# ledbord.net
KiCad netlist of a schematic drawn in EAGLE
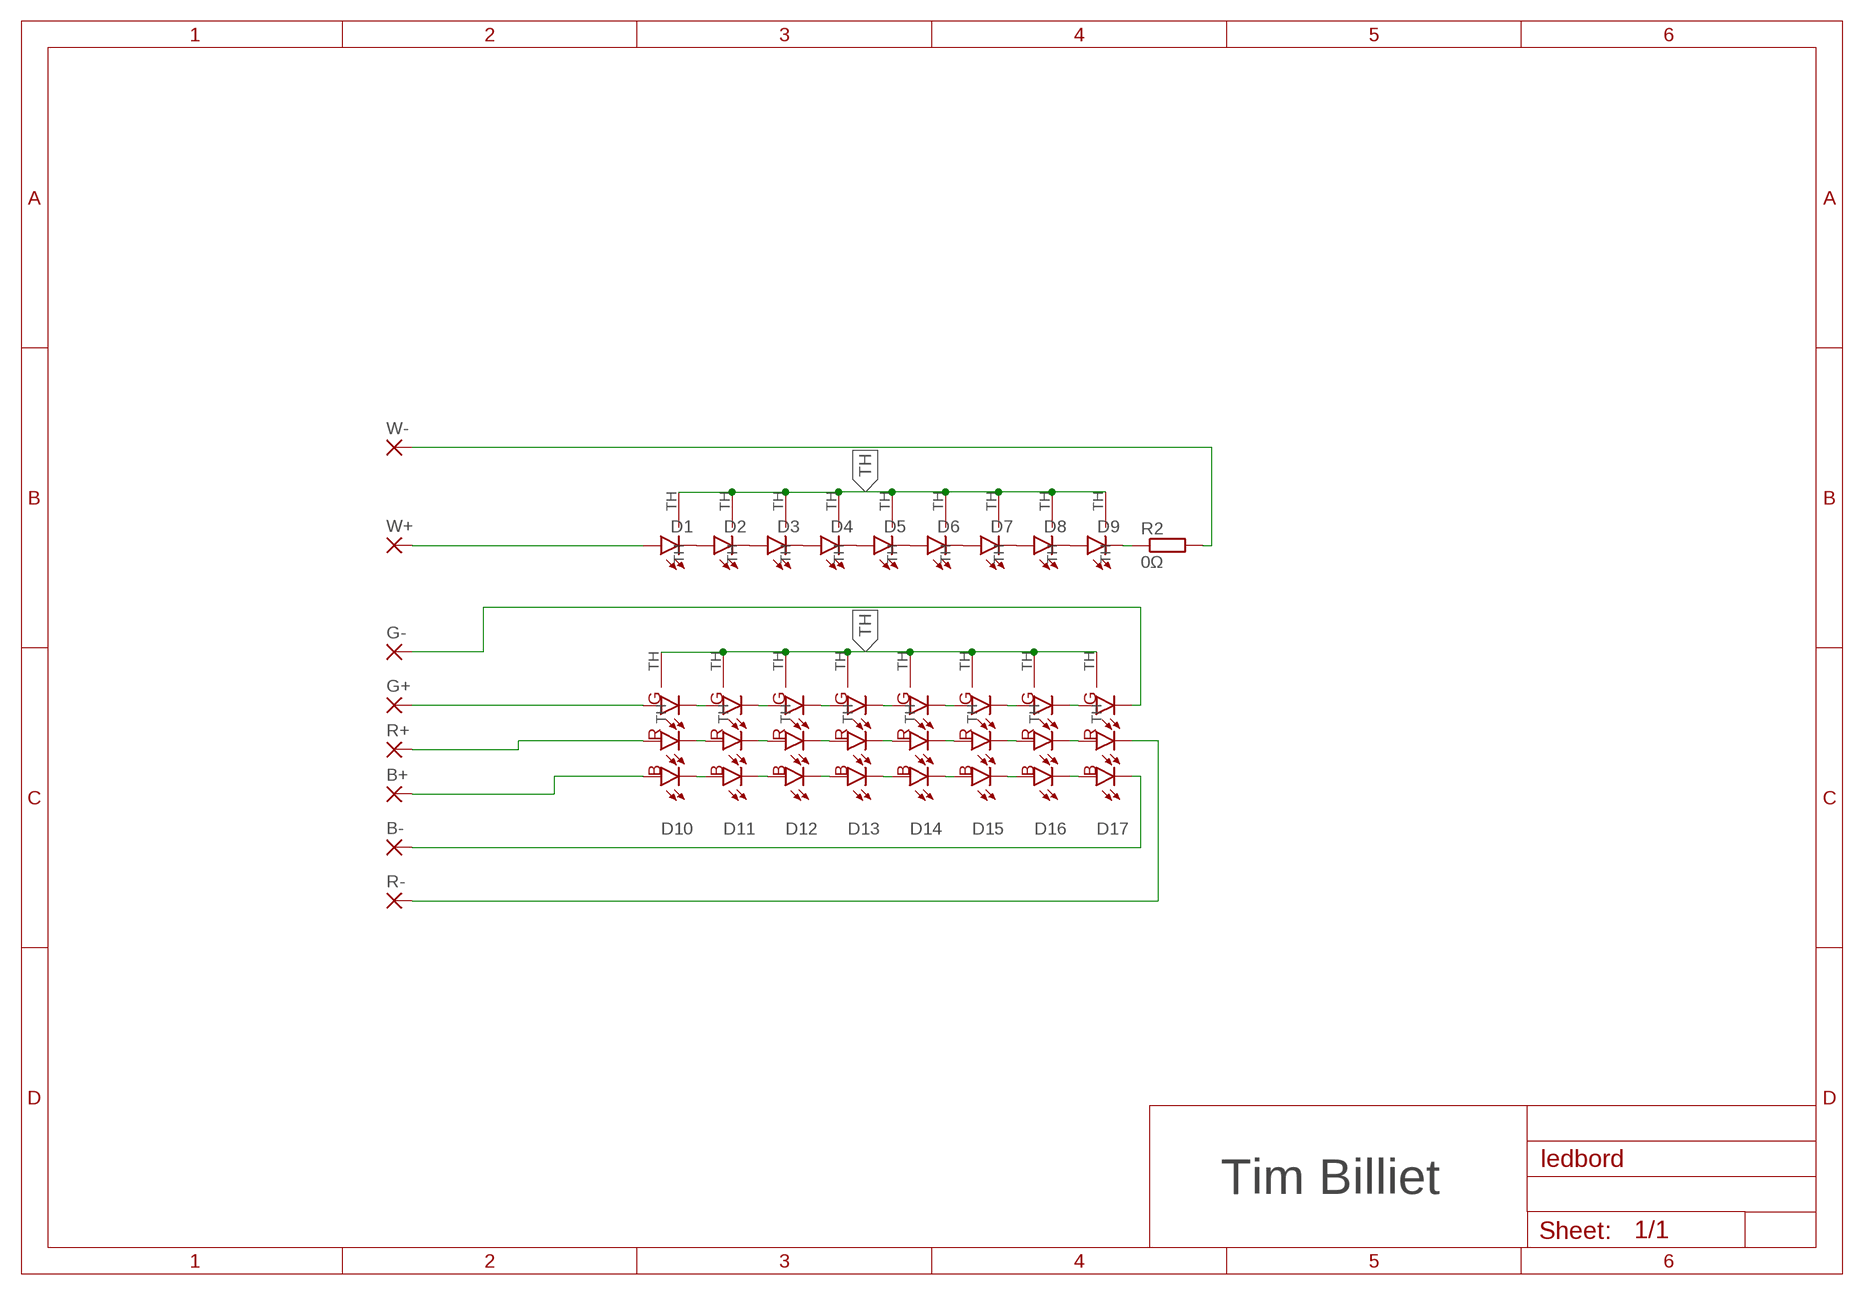
[diagram p0: schematic, sheet 1]

(export (version "E")
  (design (tool "Eeschema 10.0.6"))
  (components
    (comp (ref "B+")
      (value "SMD5")
      (footprint "eagle-import:SMD2,54-5,08")
      (libsource (lib "eagle-import") (part "SMD5"))
    )
    (comp (ref "B-")
      (value "SMD5")
      (footprint "eagle-import:SMD2,54-5,08")
      (libsource (lib "eagle-import") (part "SMD5"))
    )
    (comp (ref "D1")
      (value "HL-C3535F77W1GA-LED")
      (footprint "eagle-import:HL-C3535F77W1GA-LED")
      (libsource (lib "eagle-import") (part "HL-C3535F77W1GA-LED"))
    )
    (comp (ref "D2")
      (value "HL-C3535F77W1GA-LED")
      (footprint "eagle-import:HL-C3535F77W1GA-LED")
      (libsource (lib "eagle-import") (part "HL-C3535F77W1GA-LED"))
    )
    (comp (ref "D3")
      (value "HL-C3535F77W1GA-LED")
      (footprint "eagle-import:HL-C3535F77W1GA-LED")
      (libsource (lib "eagle-import") (part "HL-C3535F77W1GA-LED"))
    )
    (comp (ref "D4")
      (value "HL-C3535F77W1GA-LED")
      (footprint "eagle-import:HL-C3535F77W1GA-LED")
      (libsource (lib "eagle-import") (part "HL-C3535F77W1GA-LED"))
    )
    (comp (ref "D5")
      (value "HL-C3535F77W1GA-LED")
      (footprint "eagle-import:HL-C3535F77W1GA-LED")
      (libsource (lib "eagle-import") (part "HL-C3535F77W1GA-LED"))
    )
    (comp (ref "D6")
      (value "HL-C3535F77W1GA-LED")
      (footprint "eagle-import:HL-C3535F77W1GA-LED")
      (libsource (lib "eagle-import") (part "HL-C3535F77W1GA-LED"))
    )
    (comp (ref "D7")
      (value "HL-C3535F77W1GA-LED")
      (footprint "eagle-import:HL-C3535F77W1GA-LED")
      (libsource (lib "eagle-import") (part "HL-C3535F77W1GA-LED"))
    )
    (comp (ref "D8")
      (value "HL-C3535F77W1GA-LED")
      (footprint "eagle-import:HL-C3535F77W1GA-LED")
      (libsource (lib "eagle-import") (part "HL-C3535F77W1GA-LED"))
    )
    (comp (ref "D9")
      (value "HL-C3535F77W1GA-LED")
      (footprint "eagle-import:HL-C3535F77W1GA-LED")
      (libsource (lib "eagle-import") (part "HL-C3535F77W1GA-LED"))
    )
    (comp (ref "D10")
      (value "TJ-S5050UGEW5TLCBRG-A5")
      (footprint "eagle-import:TJ-S5050UGEW5TLCBRG-A5")
      (libsource (lib "eagle-import") (part "TJ-S5050UGEW5TLCBRG-A5"))
    )
    (comp (ref "D11")
      (value "TJ-S5050UGEW5TLCBRG-A5")
      (footprint "eagle-import:TJ-S5050UGEW5TLCBRG-A5")
      (libsource (lib "eagle-import") (part "TJ-S5050UGEW5TLCBRG-A5"))
    )
    (comp (ref "D12")
      (value "TJ-S5050UGEW5TLCBRG-A5")
      (footprint "eagle-import:TJ-S5050UGEW5TLCBRG-A5")
      (libsource (lib "eagle-import") (part "TJ-S5050UGEW5TLCBRG-A5"))
    )
    (comp (ref "D13")
      (value "TJ-S5050UGEW5TLCBRG-A5")
      (footprint "eagle-import:TJ-S5050UGEW5TLCBRG-A5")
      (libsource (lib "eagle-import") (part "TJ-S5050UGEW5TLCBRG-A5"))
    )
    (comp (ref "D14")
      (value "TJ-S5050UGEW5TLCBRG-A5")
      (footprint "eagle-import:TJ-S5050UGEW5TLCBRG-A5")
      (libsource (lib "eagle-import") (part "TJ-S5050UGEW5TLCBRG-A5"))
    )
    (comp (ref "D15")
      (value "TJ-S5050UGEW5TLCBRG-A5")
      (footprint "eagle-import:TJ-S5050UGEW5TLCBRG-A5")
      (libsource (lib "eagle-import") (part "TJ-S5050UGEW5TLCBRG-A5"))
    )
    (comp (ref "D16")
      (value "TJ-S5050UGEW5TLCBRG-A5")
      (footprint "eagle-import:TJ-S5050UGEW5TLCBRG-A5")
      (libsource (lib "eagle-import") (part "TJ-S5050UGEW5TLCBRG-A5"))
    )
    (comp (ref "D17")
      (value "TJ-S5050UGEW5TLCBRG-A5")
      (footprint "eagle-import:TJ-S5050UGEW5TLCBRG-A5")
      (libsource (lib "eagle-import") (part "TJ-S5050UGEW5TLCBRG-A5"))
    )
    (comp (ref "G+")
      (value "SMD5")
      (footprint "eagle-import:SMD2,54-5,08")
      (libsource (lib "eagle-import") (part "SMD5"))
    )
    (comp (ref "G-")
      (value "SMD5")
      (footprint "eagle-import:SMD2,54-5,08")
      (libsource (lib "eagle-import") (part "SMD5"))
    )
    (comp (ref "R+")
      (value "SMD5")
      (footprint "eagle-import:SMD2,54-5,08")
      (libsource (lib "eagle-import") (part "SMD5"))
    )
    (comp (ref "R-")
      (value "SMD5")
      (footprint "eagle-import:SMD2,54-5,08")
      (libsource (lib "eagle-import") (part "SMD5"))
    )
    (comp (ref "R2")
      (value "0Ω")
      (footprint "eagle-import:R2512")
      (libsource (lib "eagle-import") (part "R-EU_R2512"))
    )
    (comp (ref "W+")
      (value "SMD5")
      (footprint "eagle-import:SMD2,54-5,08")
      (libsource (lib "eagle-import") (part "SMD5"))
    )
    (comp (ref "W-")
      (value "SMD5")
      (footprint "eagle-import:SMD2,54-5,08")
      (libsource (lib "eagle-import") (part "SMD5"))
    )
  )
  (nets
    (net (code "1") (name "Net-(B+-P)") (class "Default")
      (node (ref "B+") (pin "1") (pinfunction "P_1") (pintype "passive"))
      (node (ref "D10") (pin "P6") (pinfunction "6B+_P6") (pintype "passive"))
    )
    (net (code "2") (name "Net-(B--P)") (class "Default")
      (node (ref "B-") (pin "1") (pinfunction "P_1") (pintype "passive"))
      (node (ref "D17") (pin "P1") (pinfunction "1B-_P1") (pintype "passive"))
    )
    (net (code "3") (name "Net-(D1-A)") (class "Default")
      (node (ref "D1") (pin "P$1") (pinfunction "A_P$1") (pintype "passive"))
      (node (ref "W+") (pin "1") (pinfunction "P_1") (pintype "passive"))
    )
    (net (code "4") (name "Net-(D1-C)") (class "Default")
      (node (ref "D1") (pin "P$2") (pinfunction "C_P$2") (pintype "passive"))
      (node (ref "D2") (pin "P$1") (pinfunction "A_P$1") (pintype "passive"))
    )
    (net (code "5") (name "Net-(D2-C)") (class "Default")
      (node (ref "D2") (pin "P$2") (pinfunction "C_P$2") (pintype "passive"))
      (node (ref "D3") (pin "P$1") (pinfunction "A_P$1") (pintype "passive"))
    )
    (net (code "6") (name "Net-(D3-C)") (class "Default")
      (node (ref "D3") (pin "P$2") (pinfunction "C_P$2") (pintype "passive"))
      (node (ref "D4") (pin "P$1") (pinfunction "A_P$1") (pintype "passive"))
    )
    (net (code "7") (name "Net-(D4-C)") (class "Default")
      (node (ref "D4") (pin "P$2") (pinfunction "C_P$2") (pintype "passive"))
      (node (ref "D5") (pin "P$1") (pinfunction "A_P$1") (pintype "passive"))
    )
    (net (code "8") (name "Net-(D5-C)") (class "Default")
      (node (ref "D5") (pin "P$2") (pinfunction "C_P$2") (pintype "passive"))
      (node (ref "D6") (pin "P$1") (pinfunction "A_P$1") (pintype "passive"))
    )
    (net (code "9") (name "Net-(D6-C)") (class "Default")
      (node (ref "D6") (pin "P$2") (pinfunction "C_P$2") (pintype "passive"))
      (node (ref "D7") (pin "P$1") (pinfunction "A_P$1") (pintype "passive"))
    )
    (net (code "10") (name "Net-(D7-C)") (class "Default")
      (node (ref "D7") (pin "P$2") (pinfunction "C_P$2") (pintype "passive"))
      (node (ref "D8") (pin "P$1") (pinfunction "A_P$1") (pintype "passive"))
    )
    (net (code "11") (name "Net-(D8-C)") (class "Default")
      (node (ref "D8") (pin "P$2") (pinfunction "C_P$2") (pintype "passive"))
      (node (ref "D9") (pin "P$1") (pinfunction "A_P$1") (pintype "passive"))
    )
    (net (code "12") (name "Net-(D9-C)") (class "Default")
      (node (ref "D9") (pin "P$2") (pinfunction "C_P$2") (pintype "passive"))
      (node (ref "R2") (pin "1") (pinfunction "1_1") (pintype "passive"))
    )
    (net (code "13") (name "Net-(D10-1B-)") (class "Default")
      (node (ref "D10") (pin "P1") (pinfunction "1B-_P1") (pintype "passive"))
      (node (ref "D11") (pin "P6") (pinfunction "6B+_P6") (pintype "passive"))
    )
    (net (code "14") (name "Net-(D10-2R-)") (class "Default")
      (node (ref "D10") (pin "P2") (pinfunction "2R-_P2") (pintype "passive"))
      (node (ref "D11") (pin "P5") (pinfunction "5R+_P5") (pintype "passive"))
    )
    (net (code "15") (name "Net-(D10-3G-)") (class "Default")
      (node (ref "D10") (pin "P3") (pinfunction "3G-_P3") (pintype "passive"))
      (node (ref "D11") (pin "P4") (pinfunction "4G+_P4") (pintype "passive"))
    )
    (net (code "16") (name "Net-(D10-4G+)") (class "Default")
      (node (ref "D10") (pin "P4") (pinfunction "4G+_P4") (pintype "passive"))
      (node (ref "G+") (pin "1") (pinfunction "P_1") (pintype "passive"))
    )
    (net (code "17") (name "Net-(D10-5R+)") (class "Default")
      (node (ref "D10") (pin "P5") (pinfunction "5R+_P5") (pintype "passive"))
      (node (ref "R+") (pin "1") (pinfunction "P_1") (pintype "passive"))
    )
    (net (code "18") (name "Net-(D11-1B-)") (class "Default")
      (node (ref "D11") (pin "P1") (pinfunction "1B-_P1") (pintype "passive"))
      (node (ref "D12") (pin "P6") (pinfunction "6B+_P6") (pintype "passive"))
    )
    (net (code "19") (name "Net-(D11-2R-)") (class "Default")
      (node (ref "D11") (pin "P2") (pinfunction "2R-_P2") (pintype "passive"))
      (node (ref "D12") (pin "P5") (pinfunction "5R+_P5") (pintype "passive"))
    )
    (net (code "20") (name "Net-(D11-3G-)") (class "Default")
      (node (ref "D11") (pin "P3") (pinfunction "3G-_P3") (pintype "passive"))
      (node (ref "D12") (pin "P4") (pinfunction "4G+_P4") (pintype "passive"))
    )
    (net (code "21") (name "Net-(D12-1B-)") (class "Default")
      (node (ref "D12") (pin "P1") (pinfunction "1B-_P1") (pintype "passive"))
      (node (ref "D13") (pin "P6") (pinfunction "6B+_P6") (pintype "passive"))
    )
    (net (code "22") (name "Net-(D12-2R-)") (class "Default")
      (node (ref "D12") (pin "P2") (pinfunction "2R-_P2") (pintype "passive"))
      (node (ref "D13") (pin "P5") (pinfunction "5R+_P5") (pintype "passive"))
    )
    (net (code "23") (name "Net-(D12-3G-)") (class "Default")
      (node (ref "D12") (pin "P3") (pinfunction "3G-_P3") (pintype "passive"))
      (node (ref "D13") (pin "P4") (pinfunction "4G+_P4") (pintype "passive"))
    )
    (net (code "24") (name "Net-(D13-1B-)") (class "Default")
      (node (ref "D13") (pin "P1") (pinfunction "1B-_P1") (pintype "passive"))
      (node (ref "D14") (pin "P6") (pinfunction "6B+_P6") (pintype "passive"))
    )
    (net (code "25") (name "Net-(D13-2R-)") (class "Default")
      (node (ref "D13") (pin "P2") (pinfunction "2R-_P2") (pintype "passive"))
      (node (ref "D14") (pin "P5") (pinfunction "5R+_P5") (pintype "passive"))
    )
    (net (code "26") (name "Net-(D13-3G-)") (class "Default")
      (node (ref "D13") (pin "P3") (pinfunction "3G-_P3") (pintype "passive"))
      (node (ref "D14") (pin "P4") (pinfunction "4G+_P4") (pintype "passive"))
    )
    (net (code "27") (name "Net-(D14-1B-)") (class "Default")
      (node (ref "D14") (pin "P1") (pinfunction "1B-_P1") (pintype "passive"))
      (node (ref "D15") (pin "P6") (pinfunction "6B+_P6") (pintype "passive"))
    )
    (net (code "28") (name "Net-(D14-2R-)") (class "Default")
      (node (ref "D14") (pin "P2") (pinfunction "2R-_P2") (pintype "passive"))
      (node (ref "D15") (pin "P5") (pinfunction "5R+_P5") (pintype "passive"))
    )
    (net (code "29") (name "Net-(D14-3G-)") (class "Default")
      (node (ref "D14") (pin "P3") (pinfunction "3G-_P3") (pintype "passive"))
      (node (ref "D15") (pin "P4") (pinfunction "4G+_P4") (pintype "passive"))
    )
    (net (code "30") (name "Net-(D15-1B-)") (class "Default")
      (node (ref "D15") (pin "P1") (pinfunction "1B-_P1") (pintype "passive"))
      (node (ref "D16") (pin "P6") (pinfunction "6B+_P6") (pintype "passive"))
    )
    (net (code "31") (name "Net-(D15-2R-)") (class "Default")
      (node (ref "D15") (pin "P2") (pinfunction "2R-_P2") (pintype "passive"))
      (node (ref "D16") (pin "P5") (pinfunction "5R+_P5") (pintype "passive"))
    )
    (net (code "32") (name "Net-(D15-3G-)") (class "Default")
      (node (ref "D15") (pin "P3") (pinfunction "3G-_P3") (pintype "passive"))
      (node (ref "D16") (pin "P4") (pinfunction "4G+_P4") (pintype "passive"))
    )
    (net (code "33") (name "Net-(D16-1B-)") (class "Default")
      (node (ref "D16") (pin "P1") (pinfunction "1B-_P1") (pintype "passive"))
      (node (ref "D17") (pin "P6") (pinfunction "6B+_P6") (pintype "passive"))
    )
    (net (code "34") (name "Net-(D16-2R-)") (class "Default")
      (node (ref "D16") (pin "P2") (pinfunction "2R-_P2") (pintype "passive"))
      (node (ref "D17") (pin "P5") (pinfunction "5R+_P5") (pintype "passive"))
    )
    (net (code "35") (name "Net-(D16-3G-)") (class "Default")
      (node (ref "D16") (pin "P3") (pinfunction "3G-_P3") (pintype "passive"))
      (node (ref "D17") (pin "P4") (pinfunction "4G+_P4") (pintype "passive"))
    )
    (net (code "36") (name "Net-(D17-2R-)") (class "Default")
      (node (ref "D17") (pin "P2") (pinfunction "2R-_P2") (pintype "passive"))
      (node (ref "R-") (pin "1") (pinfunction "P_1") (pintype "passive"))
    )
    (net (code "37") (name "Net-(D17-3G-)") (class "Default")
      (node (ref "D17") (pin "P3") (pinfunction "3G-_P3") (pintype "passive"))
      (node (ref "G-") (pin "1") (pinfunction "P_1") (pintype "passive"))
    )
    (net (code "38") (name "Net-(W--P)") (class "Default")
      (node (ref "R2") (pin "2") (pinfunction "2_2") (pintype "passive"))
      (node (ref "W-") (pin "1") (pinfunction "P_1") (pintype "passive"))
    )
    (net (code "39") (name "TH") (class "Default")
      (node (ref "D1") (pin "TH") (pinfunction "TH_TH") (pintype "bidirectional"))
      (node (ref "D10") (pin "TH") (pinfunction "TH_TH") (pintype "bidirectional"))
      (node (ref "D11") (pin "TH") (pinfunction "TH_TH") (pintype "bidirectional"))
      (node (ref "D12") (pin "TH") (pinfunction "TH_TH") (pintype "bidirectional"))
      (node (ref "D13") (pin "TH") (pinfunction "TH_TH") (pintype "bidirectional"))
      (node (ref "D14") (pin "TH") (pinfunction "TH_TH") (pintype "bidirectional"))
      (node (ref "D15") (pin "TH") (pinfunction "TH_TH") (pintype "bidirectional"))
      (node (ref "D16") (pin "TH") (pinfunction "TH_TH") (pintype "bidirectional"))
      (node (ref "D17") (pin "TH") (pinfunction "TH_TH") (pintype "bidirectional"))
      (node (ref "D2") (pin "TH") (pinfunction "TH_TH") (pintype "bidirectional"))
      (node (ref "D3") (pin "TH") (pinfunction "TH_TH") (pintype "bidirectional"))
      (node (ref "D4") (pin "TH") (pinfunction "TH_TH") (pintype "bidirectional"))
      (node (ref "D5") (pin "TH") (pinfunction "TH_TH") (pintype "bidirectional"))
      (node (ref "D6") (pin "TH") (pinfunction "TH_TH") (pintype "bidirectional"))
      (node (ref "D7") (pin "TH") (pinfunction "TH_TH") (pintype "bidirectional"))
      (node (ref "D8") (pin "TH") (pinfunction "TH_TH") (pintype "bidirectional"))
      (node (ref "D9") (pin "TH") (pinfunction "TH_TH") (pintype "bidirectional"))
    )
  )
)
